# StepperMotorDrivers.net
KiCad netlist of a schematic drawn in Altium Designer
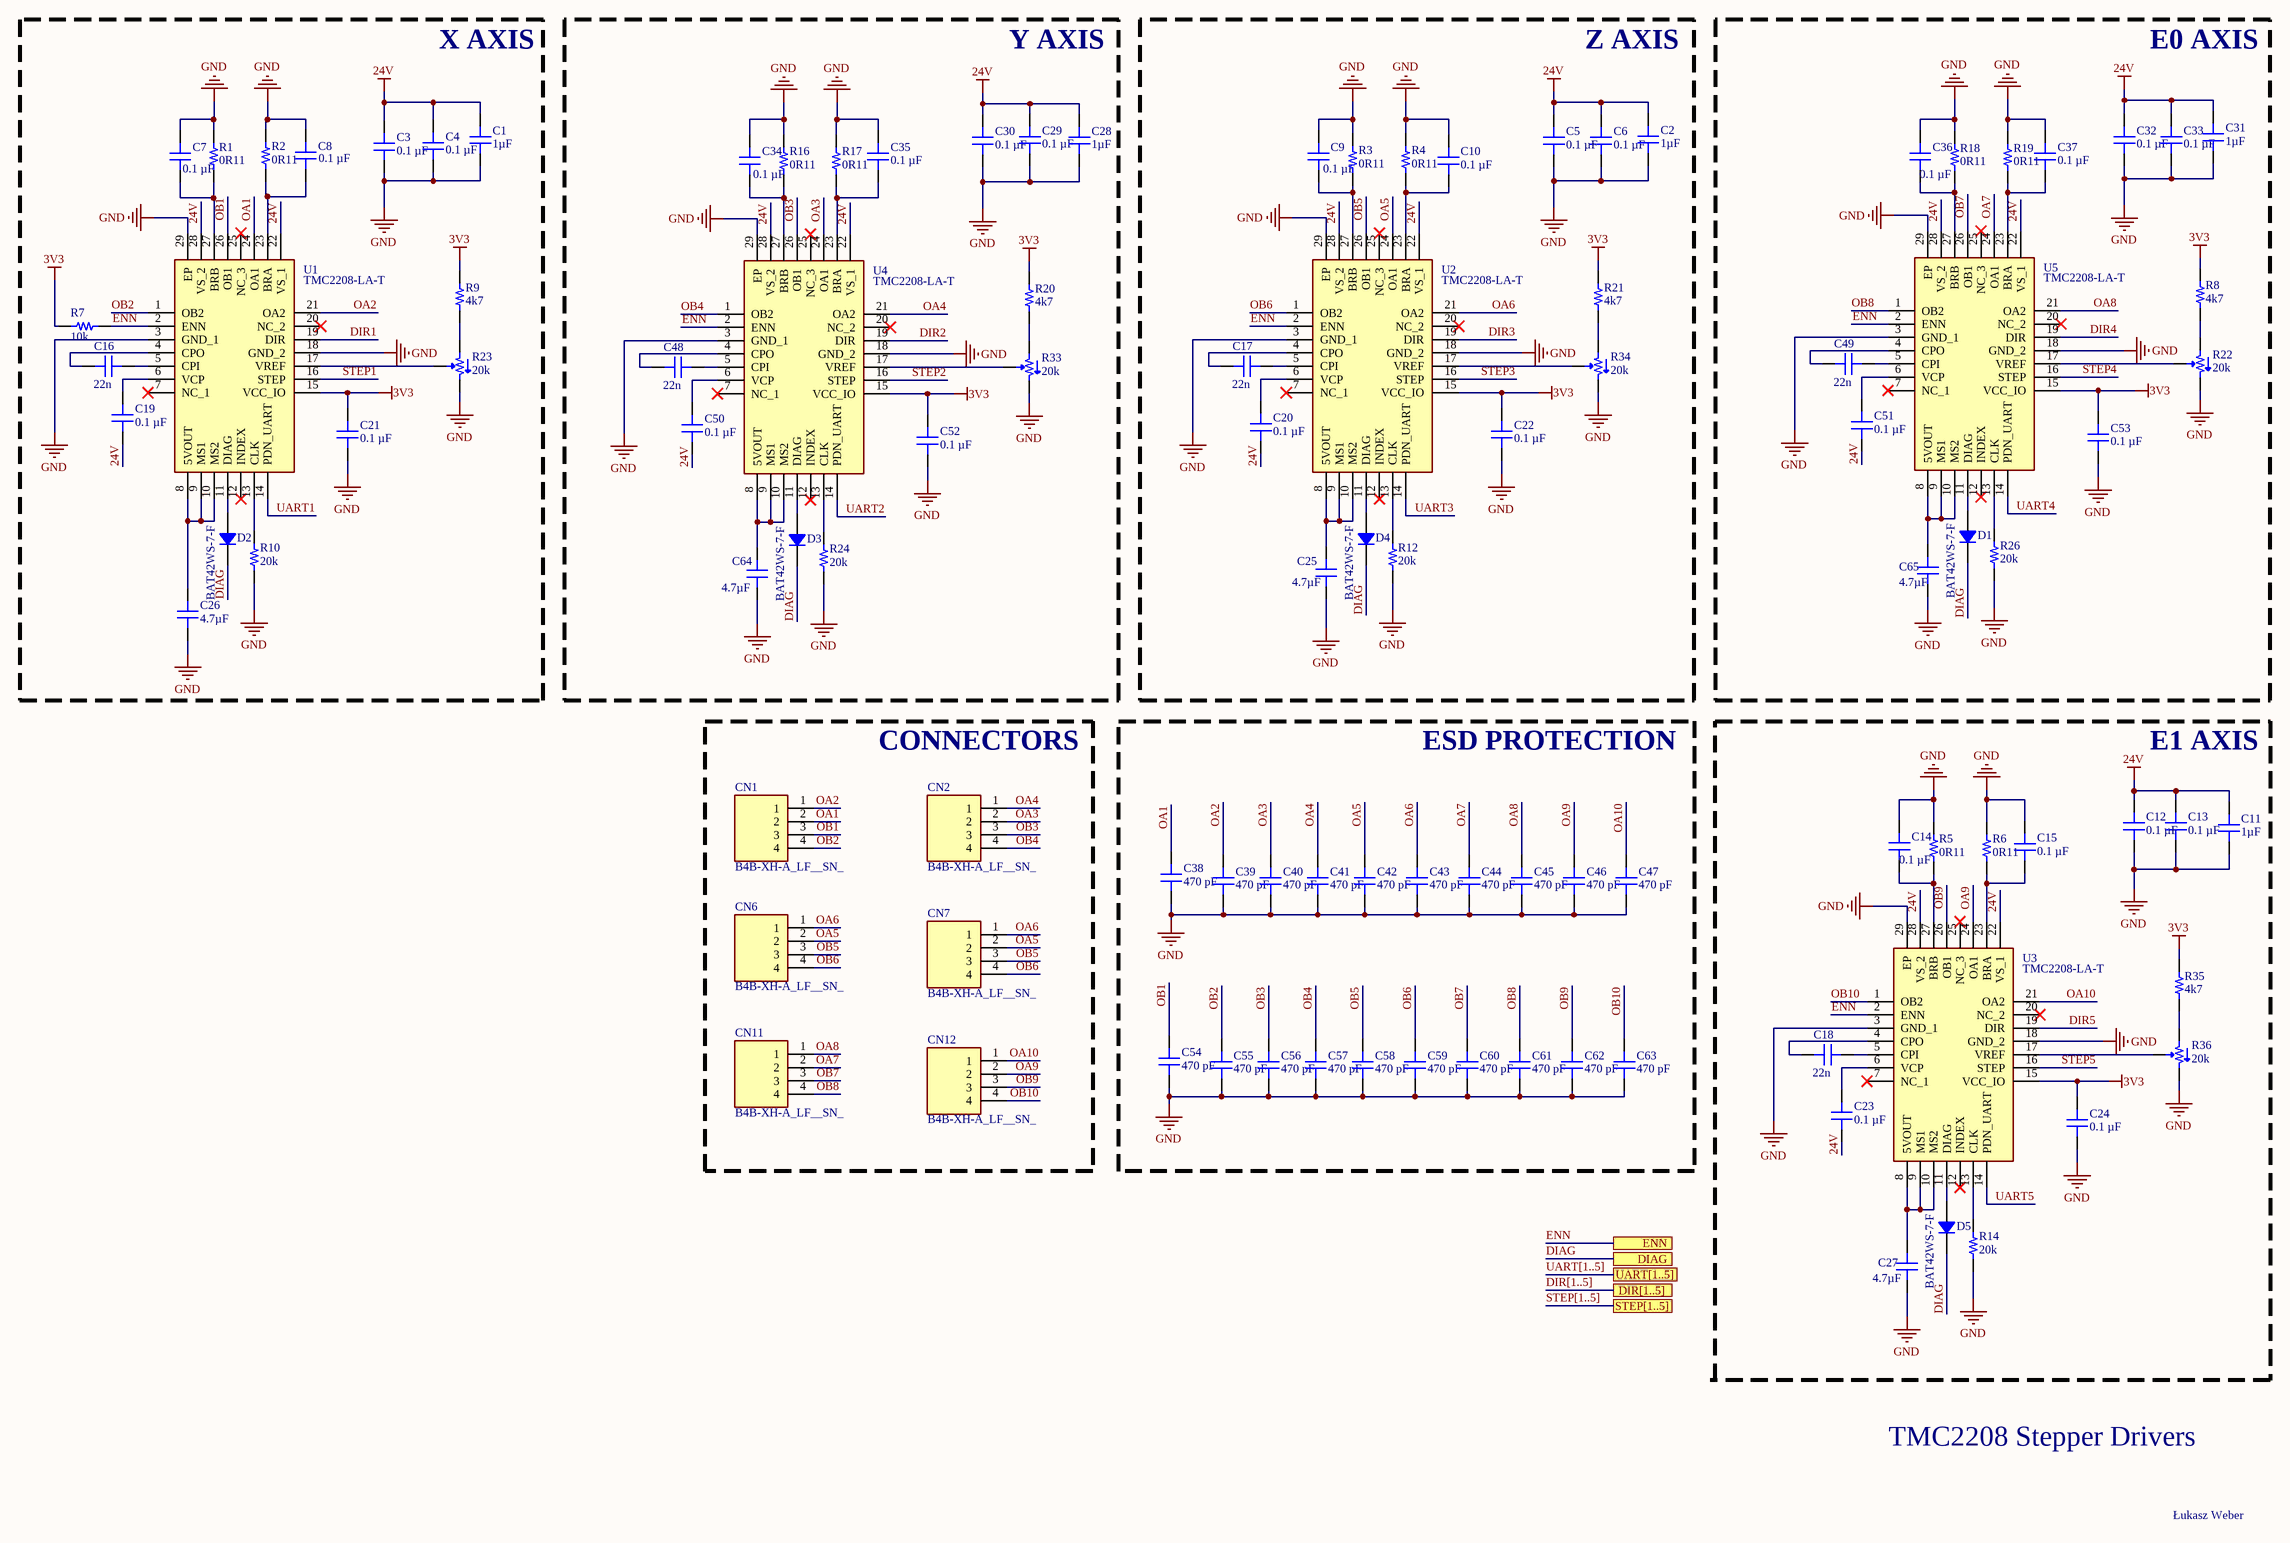
[diagram p0: StepperMotorDrivers.SchDoc]

(export (version "E")
  (design (tool "Eeschema 10.0.6"))
  (components
    (comp (ref "C1")
      (value "1µF")
      (footprint "CAP 0603_1608")
      (description "CAP CER 1UF 50V X7R 0603")
      (fields (field (name "PART NUMBER") "06035C105KAT2A") (field (name "MANUFACTURER") "AVX Corporation"))
      (libsource (lib "Celestial Altium Library - altium_library") (part "Capacitor"))
    )
    (comp (ref "C2")
      (value "1µF")
      (footprint "CAP 0603_1608")
      (description "CAP CER 1UF 50V X7R 0603")
      (fields (field (name "PART NUMBER") "06035C105KAT2A") (field (name "MANUFACTURER") "AVX Corporation"))
      (libsource (lib "Celestial Altium Library - altium_library") (part "Capacitor"))
    )
    (comp (ref "C3")
      (value "0.1 µF")
      (footprint "CAP 0603_1608")
      (description "CAP CER 0.1UF 100V X7R 0603")
      (fields
        (field (name "PART NUMBER") "0603B104K101CT")
        (field (name "MANUFACTURER") "Walsin Technology Corporation")
      )
      (libsource (lib "Celestial Altium Library - altium_library") (part "Capacitor"))
    )
    (comp (ref "C4")
      (value "0.1 µF")
      (footprint "CAP 0603_1608")
      (description "CAP CER 0.1UF 100V X7R 0603")
      (fields
        (field (name "PART NUMBER") "0603B104K101CT")
        (field (name "MANUFACTURER") "Walsin Technology Corporation")
      )
      (libsource (lib "Celestial Altium Library - altium_library") (part "Capacitor"))
    )
    (comp (ref "C5")
      (value "0.1 µF")
      (footprint "CAP 0603_1608")
      (description "CAP CER 0.1UF 100V X7R 0603")
      (fields
        (field (name "PART NUMBER") "0603B104K101CT")
        (field (name "MANUFACTURER") "Walsin Technology Corporation")
      )
      (libsource (lib "Celestial Altium Library - altium_library") (part "Capacitor"))
    )
    (comp (ref "C6")
      (value "0.1 µF")
      (footprint "CAP 0603_1608")
      (description "CAP CER 0.1UF 100V X7R 0603")
      (fields
        (field (name "PART NUMBER") "0603B104K101CT")
        (field (name "MANUFACTURER") "Walsin Technology Corporation")
      )
      (libsource (lib "Celestial Altium Library - altium_library") (part "Capacitor"))
    )
    (comp (ref "C7")
      (value "0.1 µF")
      (footprint "CAP 0603_1608")
      (description "CAP CER 0.1UF 100V X7R 0603")
      (fields
        (field (name "PART NUMBER") "0603B104K101CT")
        (field (name "MANUFACTURER") "Walsin Technology Corporation")
      )
      (libsource (lib "Celestial Altium Library - altium_library") (part "Capacitor"))
    )
    (comp (ref "C8")
      (value "0.1 µF")
      (footprint "CAP 0603_1608")
      (description "CAP CER 0.1UF 100V X7R 0603")
      (fields
        (field (name "PART NUMBER") "0603B104K101CT")
        (field (name "MANUFACTURER") "Walsin Technology Corporation")
      )
      (libsource (lib "Celestial Altium Library - altium_library") (part "Capacitor"))
    )
    (comp (ref "C9")
      (value "0.1 µF")
      (footprint "CAP 0603_1608")
      (description "CAP CER 0.1UF 100V X7R 0603")
      (fields
        (field (name "PART NUMBER") "0603B104K101CT")
        (field (name "MANUFACTURER") "Walsin Technology Corporation")
      )
      (libsource (lib "Celestial Altium Library - altium_library") (part "Capacitor"))
    )
    (comp (ref "C10")
      (value "0.1 µF")
      (footprint "CAP 0603_1608")
      (description "CAP CER 0.1UF 100V X7R 0603")
      (fields
        (field (name "PART NUMBER") "0603B104K101CT")
        (field (name "MANUFACTURER") "Walsin Technology Corporation")
      )
      (libsource (lib "Celestial Altium Library - altium_library") (part "Capacitor"))
    )
    (comp (ref "C11")
      (value "1µF")
      (footprint "CAP 0603_1608")
      (description "CAP CER 1UF 50V X7R 0603")
      (fields (field (name "PART NUMBER") "06035C105KAT2A") (field (name "MANUFACTURER") "AVX Corporation"))
      (libsource (lib "Celestial Altium Library - altium_library") (part "Capacitor"))
    )
    (comp (ref "C12")
      (value "0.1 µF")
      (footprint "CAP 0603_1608")
      (description "CAP CER 0.1UF 100V X7R 0603")
      (fields
        (field (name "PART NUMBER") "0603B104K101CT")
        (field (name "MANUFACTURER") "Walsin Technology Corporation")
      )
      (libsource (lib "Celestial Altium Library - altium_library") (part "Capacitor"))
    )
    (comp (ref "C13")
      (value "0.1 µF")
      (footprint "CAP 0603_1608")
      (description "CAP CER 0.1UF 100V X7R 0603")
      (fields
        (field (name "PART NUMBER") "0603B104K101CT")
        (field (name "MANUFACTURER") "Walsin Technology Corporation")
      )
      (libsource (lib "Celestial Altium Library - altium_library") (part "Capacitor"))
    )
    (comp (ref "C14")
      (value "0.1 µF")
      (footprint "CAP 0603_1608")
      (description "CAP CER 0.1UF 100V X7R 0603")
      (fields
        (field (name "PART NUMBER") "0603B104K101CT")
        (field (name "MANUFACTURER") "Walsin Technology Corporation")
      )
      (libsource (lib "Celestial Altium Library - altium_library") (part "Capacitor"))
    )
    (comp (ref "C15")
      (value "0.1 µF")
      (footprint "CAP 0603_1608")
      (description "CAP CER 0.1UF 100V X7R 0603")
      (fields
        (field (name "PART NUMBER") "0603B104K101CT")
        (field (name "MANUFACTURER") "Walsin Technology Corporation")
      )
      (libsource (lib "Celestial Altium Library - altium_library") (part "Capacitor"))
    )
    (comp (ref "C16")
      (value "22n")
      (footprint "CAP 0603_1608")
      (description "CAP CER 2200PF 50V NP0 0603")
      (fields (field (name "PART NUMBER") "C0603C222G5GAC7867") (field (name "MANUFACTURER") "KEMET"))
      (libsource (lib "Celestial Altium Library - altium_library") (part "Capacitor"))
    )
    (comp (ref "C17")
      (value "22n")
      (footprint "CAP 0603_1608")
      (description "CAP CER 2200PF 50V NP0 0603")
      (fields (field (name "PART NUMBER") "C0603C222G5GAC7867") (field (name "MANUFACTURER") "KEMET"))
      (libsource (lib "Celestial Altium Library - altium_library") (part "Capacitor"))
    )
    (comp (ref "C18")
      (value "22n")
      (footprint "CAP 0603_1608")
      (description "CAP CER 2200PF 50V NP0 0603")
      (fields (field (name "PART NUMBER") "C0603C222G5GAC7867") (field (name "MANUFACTURER") "KEMET"))
      (libsource (lib "Celestial Altium Library - altium_library") (part "Capacitor"))
    )
    (comp (ref "C19")
      (value "0.1 µF")
      (footprint "CAP 0603_1608")
      (description "CAP CER 0.1UF 100V X7R 0603")
      (fields
        (field (name "PART NUMBER") "0603B104K101CT")
        (field (name "MANUFACTURER") "Walsin Technology Corporation")
      )
      (libsource (lib "Celestial Altium Library - altium_library") (part "Capacitor"))
    )
    (comp (ref "C20")
      (value "0.1 µF")
      (footprint "CAP 0603_1608")
      (description "CAP CER 0.1UF 100V X7R 0603")
      (fields
        (field (name "PART NUMBER") "0603B104K101CT")
        (field (name "MANUFACTURER") "Walsin Technology Corporation")
      )
      (libsource (lib "Celestial Altium Library - altium_library") (part "Capacitor"))
    )
    (comp (ref "C21")
      (value "0.1 µF")
      (footprint "CAP 0603_1608")
      (description "CAP CER 0.1UF 100V X7R 0603")
      (fields
        (field (name "PART NUMBER") "0603B104K101CT")
        (field (name "MANUFACTURER") "Walsin Technology Corporation")
      )
      (libsource (lib "Celestial Altium Library - altium_library") (part "Capacitor"))
    )
    (comp (ref "C22")
      (value "0.1 µF")
      (footprint "CAP 0603_1608")
      (description "CAP CER 0.1UF 100V X7R 0603")
      (fields
        (field (name "PART NUMBER") "0603B104K101CT")
        (field (name "MANUFACTURER") "Walsin Technology Corporation")
      )
      (libsource (lib "Celestial Altium Library - altium_library") (part "Capacitor"))
    )
    (comp (ref "C23")
      (value "0.1 µF")
      (footprint "CAP 0603_1608")
      (description "CAP CER 0.1UF 100V X7R 0603")
      (fields
        (field (name "PART NUMBER") "0603B104K101CT")
        (field (name "MANUFACTURER") "Walsin Technology Corporation")
      )
      (libsource (lib "Celestial Altium Library - altium_library") (part "Capacitor"))
    )
    (comp (ref "C24")
      (value "0.1 µF")
      (footprint "CAP 0603_1608")
      (description "CAP CER 0.1UF 100V X7R 0603")
      (fields
        (field (name "PART NUMBER") "0603B104K101CT")
        (field (name "MANUFACTURER") "Walsin Technology Corporation")
      )
      (libsource (lib "Celestial Altium Library - altium_library") (part "Capacitor"))
    )
    (comp (ref "C25")
      (value "4.7µF")
      (footprint "CAP 0603_1608")
      (description "CAP CER 4.7UF 6.3V X5R 0603")
      (fields (field (name "PART NUMBER") "06036D475MAT2A") (field (name "MANUFACTURER") "AVX Corporation"))
      (libsource (lib "Celestial Altium Library - altium_library") (part "Capacitor"))
    )
    (comp (ref "C26")
      (value "4.7µF")
      (footprint "CAP 0603_1608")
      (description "CAP CER 4.7UF 6.3V X5R 0603")
      (fields (field (name "PART NUMBER") "06036D475MAT2A") (field (name "MANUFACTURER") "AVX Corporation"))
      (libsource (lib "Celestial Altium Library - altium_library") (part "Capacitor"))
    )
    (comp (ref "C27")
      (value "4.7µF")
      (footprint "CAP 0603_1608")
      (description "CAP CER 4.7UF 6.3V X5R 0603")
      (fields (field (name "PART NUMBER") "06036D475MAT2A") (field (name "MANUFACTURER") "AVX Corporation"))
      (libsource (lib "Celestial Altium Library - altium_library") (part "Capacitor"))
    )
    (comp (ref "C28")
      (value "1µF")
      (footprint "CAP 0603_1608")
      (description "CAP CER 1UF 50V X7R 0603")
      (fields (field (name "PART NUMBER") "06035C105KAT2A") (field (name "MANUFACTURER") "AVX Corporation"))
      (libsource (lib "Celestial Altium Library - altium_library") (part "Capacitor"))
    )
    (comp (ref "C29")
      (value "0.1 µF")
      (footprint "CAP 0603_1608")
      (description "CAP CER 0.1UF 100V X7R 0603")
      (fields
        (field (name "PART NUMBER") "0603B104K101CT")
        (field (name "MANUFACTURER") "Walsin Technology Corporation")
      )
      (libsource (lib "Celestial Altium Library - altium_library") (part "Capacitor"))
    )
    (comp (ref "C30")
      (value "0.1 µF")
      (footprint "CAP 0603_1608")
      (description "CAP CER 0.1UF 100V X7R 0603")
      (fields
        (field (name "PART NUMBER") "0603B104K101CT")
        (field (name "MANUFACTURER") "Walsin Technology Corporation")
      )
      (libsource (lib "Celestial Altium Library - altium_library") (part "Capacitor"))
    )
    (comp (ref "C31")
      (value "1µF")
      (footprint "CAP 0603_1608")
      (description "CAP CER 1UF 50V X7R 0603")
      (fields (field (name "PART NUMBER") "06035C105KAT2A") (field (name "MANUFACTURER") "AVX Corporation"))
      (libsource (lib "Celestial Altium Library - altium_library") (part "Capacitor"))
    )
    (comp (ref "C32")
      (value "0.1 µF")
      (footprint "CAP 0603_1608")
      (description "CAP CER 0.1UF 100V X7R 0603")
      (fields
        (field (name "PART NUMBER") "0603B104K101CT")
        (field (name "MANUFACTURER") "Walsin Technology Corporation")
      )
      (libsource (lib "Celestial Altium Library - altium_library") (part "Capacitor"))
    )
    (comp (ref "C33")
      (value "0.1 µF")
      (footprint "CAP 0603_1608")
      (description "CAP CER 0.1UF 100V X7R 0603")
      (fields
        (field (name "PART NUMBER") "0603B104K101CT")
        (field (name "MANUFACTURER") "Walsin Technology Corporation")
      )
      (libsource (lib "Celestial Altium Library - altium_library") (part "Capacitor"))
    )
    (comp (ref "C34")
      (value "0.1 µF")
      (footprint "CAP 0603_1608")
      (description "CAP CER 0.1UF 100V X7R 0603")
      (fields
        (field (name "PART NUMBER") "0603B104K101CT")
        (field (name "MANUFACTURER") "Walsin Technology Corporation")
      )
      (libsource (lib "Celestial Altium Library - altium_library") (part "Capacitor"))
    )
    (comp (ref "C35")
      (value "0.1 µF")
      (footprint "CAP 0603_1608")
      (description "CAP CER 0.1UF 100V X7R 0603")
      (fields
        (field (name "PART NUMBER") "0603B104K101CT")
        (field (name "MANUFACTURER") "Walsin Technology Corporation")
      )
      (libsource (lib "Celestial Altium Library - altium_library") (part "Capacitor"))
    )
    (comp (ref "C36")
      (value "0.1 µF")
      (footprint "CAP 0603_1608")
      (description "CAP CER 0.1UF 100V X7R 0603")
      (fields
        (field (name "PART NUMBER") "0603B104K101CT")
        (field (name "MANUFACTURER") "Walsin Technology Corporation")
      )
      (libsource (lib "Celestial Altium Library - altium_library") (part "Capacitor"))
    )
    (comp (ref "C37")
      (value "0.1 µF")
      (footprint "CAP 0603_1608")
      (description "CAP CER 0.1UF 100V X7R 0603")
      (fields
        (field (name "PART NUMBER") "0603B104K101CT")
        (field (name "MANUFACTURER") "Walsin Technology Corporation")
      )
      (libsource (lib "Celestial Altium Library - altium_library") (part "Capacitor"))
    )
    (comp (ref "C38")
      (value "470 pF")
      (footprint "CAP 0603_1608")
      (description "CAP CER 0603 470PF 5% X7R 50V FL")
      (fields (field (name "PART NUMBER") "C0603X471J5RAC7867") (field (name "MANUFACTURER") "KEMET"))
      (libsource (lib "Celestial Altium Library - altium_library") (part "Capacitor"))
    )
    (comp (ref "C39")
      (value "470 pF")
      (footprint "CAP 0603_1608")
      (description "CAP CER 0603 470PF 5% X7R 50V FL")
      (fields (field (name "PART NUMBER") "C0603X471J5RAC7867") (field (name "MANUFACTURER") "KEMET"))
      (libsource (lib "Celestial Altium Library - altium_library") (part "Capacitor"))
    )
    (comp (ref "C40")
      (value "470 pF")
      (footprint "CAP 0603_1608")
      (description "CAP CER 0603 470PF 5% X7R 50V FL")
      (fields (field (name "PART NUMBER") "C0603X471J5RAC7867") (field (name "MANUFACTURER") "KEMET"))
      (libsource (lib "Celestial Altium Library - altium_library") (part "Capacitor"))
    )
    (comp (ref "C41")
      (value "470 pF")
      (footprint "CAP 0603_1608")
      (description "CAP CER 0603 470PF 5% X7R 50V FL")
      (fields (field (name "PART NUMBER") "C0603X471J5RAC7867") (field (name "MANUFACTURER") "KEMET"))
      (libsource (lib "Celestial Altium Library - altium_library") (part "Capacitor"))
    )
    (comp (ref "C42")
      (value "470 pF")
      (footprint "CAP 0603_1608")
      (description "CAP CER 0603 470PF 5% X7R 50V FL")
      (fields (field (name "PART NUMBER") "C0603X471J5RAC7867") (field (name "MANUFACTURER") "KEMET"))
      (libsource (lib "Celestial Altium Library - altium_library") (part "Capacitor"))
    )
    (comp (ref "C43")
      (value "470 pF")
      (footprint "CAP 0603_1608")
      (description "CAP CER 0603 470PF 5% X7R 50V FL")
      (fields (field (name "PART NUMBER") "C0603X471J5RAC7867") (field (name "MANUFACTURER") "KEMET"))
      (libsource (lib "Celestial Altium Library - altium_library") (part "Capacitor"))
    )
    (comp (ref "C44")
      (value "470 pF")
      (footprint "CAP 0603_1608")
      (description "CAP CER 0603 470PF 5% X7R 50V FL")
      (fields (field (name "PART NUMBER") "C0603X471J5RAC7867") (field (name "MANUFACTURER") "KEMET"))
      (libsource (lib "Celestial Altium Library - altium_library") (part "Capacitor"))
    )
    (comp (ref "C45")
      (value "470 pF")
      (footprint "CAP 0603_1608")
      (description "CAP CER 0603 470PF 5% X7R 50V FL")
      (fields (field (name "PART NUMBER") "C0603X471J5RAC7867") (field (name "MANUFACTURER") "KEMET"))
      (libsource (lib "Celestial Altium Library - altium_library") (part "Capacitor"))
    )
    (comp (ref "C46")
      (value "470 pF")
      (footprint "CAP 0603_1608")
      (description "CAP CER 0603 470PF 5% X7R 50V FL")
      (fields (field (name "PART NUMBER") "C0603X471J5RAC7867") (field (name "MANUFACTURER") "KEMET"))
      (libsource (lib "Celestial Altium Library - altium_library") (part "Capacitor"))
    )
    (comp (ref "C47")
      (value "470 pF")
      (footprint "CAP 0603_1608")
      (description "CAP CER 0603 470PF 5% X7R 50V FL")
      (fields (field (name "PART NUMBER") "C0603X471J5RAC7867") (field (name "MANUFACTURER") "KEMET"))
      (libsource (lib "Celestial Altium Library - altium_library") (part "Capacitor"))
    )
    (comp (ref "C48")
      (value "22n")
      (footprint "CAP 0603_1608")
      (description "CAP CER 2200PF 50V NP0 0603")
      (fields (field (name "PART NUMBER") "C0603C222G5GAC7867") (field (name "MANUFACTURER") "KEMET"))
      (libsource (lib "Celestial Altium Library - altium_library") (part "Capacitor"))
    )
    (comp (ref "C49")
      (value "22n")
      (footprint "CAP 0603_1608")
      (description "CAP CER 2200PF 50V NP0 0603")
      (fields (field (name "PART NUMBER") "C0603C222G5GAC7867") (field (name "MANUFACTURER") "KEMET"))
      (libsource (lib "Celestial Altium Library - altium_library") (part "Capacitor"))
    )
    (comp (ref "C50")
      (value "0.1 µF")
      (footprint "CAP 0603_1608")
      (description "CAP CER 0.1UF 100V X7R 0603")
      (fields
        (field (name "PART NUMBER") "0603B104K101CT")
        (field (name "MANUFACTURER") "Walsin Technology Corporation")
      )
      (libsource (lib "Celestial Altium Library - altium_library") (part "Capacitor"))
    )
    (comp (ref "C51")
      (value "0.1 µF")
      (footprint "CAP 0603_1608")
      (description "CAP CER 0.1UF 100V X7R 0603")
      (fields
        (field (name "PART NUMBER") "0603B104K101CT")
        (field (name "MANUFACTURER") "Walsin Technology Corporation")
      )
      (libsource (lib "Celestial Altium Library - altium_library") (part "Capacitor"))
    )
    (comp (ref "C52")
      (value "0.1 µF")
      (footprint "CAP 0603_1608")
      (description "CAP CER 0.1UF 100V X7R 0603")
      (fields
        (field (name "PART NUMBER") "0603B104K101CT")
        (field (name "MANUFACTURER") "Walsin Technology Corporation")
      )
      (libsource (lib "Celestial Altium Library - altium_library") (part "Capacitor"))
    )
    (comp (ref "C53")
      (value "0.1 µF")
      (footprint "CAP 0603_1608")
      (description "CAP CER 0.1UF 100V X7R 0603")
      (fields
        (field (name "PART NUMBER") "0603B104K101CT")
        (field (name "MANUFACTURER") "Walsin Technology Corporation")
      )
      (libsource (lib "Celestial Altium Library - altium_library") (part "Capacitor"))
    )
    (comp (ref "C54")
      (value "470 pF")
      (footprint "CAP 0603_1608")
      (description "CAP CER 0603 470PF 5% X7R 50V FL")
      (fields (field (name "PART NUMBER") "C0603X471J5RAC7867") (field (name "MANUFACTURER") "KEMET"))
      (libsource (lib "Celestial Altium Library - altium_library") (part "Capacitor"))
    )
    (comp (ref "C55")
      (value "470 pF")
      (footprint "CAP 0603_1608")
      (description "CAP CER 0603 470PF 5% X7R 50V FL")
      (fields (field (name "PART NUMBER") "C0603X471J5RAC7867") (field (name "MANUFACTURER") "KEMET"))
      (libsource (lib "Celestial Altium Library - altium_library") (part "Capacitor"))
    )
    (comp (ref "C56")
      (value "470 pF")
      (footprint "CAP 0603_1608")
      (description "CAP CER 0603 470PF 5% X7R 50V FL")
      (fields (field (name "PART NUMBER") "C0603X471J5RAC7867") (field (name "MANUFACTURER") "KEMET"))
      (libsource (lib "Celestial Altium Library - altium_library") (part "Capacitor"))
    )
    (comp (ref "C57")
      (value "470 pF")
      (footprint "CAP 0603_1608")
      (description "CAP CER 0603 470PF 5% X7R 50V FL")
      (fields (field (name "PART NUMBER") "C0603X471J5RAC7867") (field (name "MANUFACTURER") "KEMET"))
      (libsource (lib "Celestial Altium Library - altium_library") (part "Capacitor"))
    )
    (comp (ref "C58")
      (value "470 pF")
      (footprint "CAP 0603_1608")
      (description "CAP CER 0603 470PF 5% X7R 50V FL")
      (fields (field (name "PART NUMBER") "C0603X471J5RAC7867") (field (name "MANUFACTURER") "KEMET"))
      (libsource (lib "Celestial Altium Library - altium_library") (part "Capacitor"))
    )
    (comp (ref "C59")
      (value "470 pF")
      (footprint "CAP 0603_1608")
      (description "CAP CER 0603 470PF 5% X7R 50V FL")
      (fields (field (name "PART NUMBER") "C0603X471J5RAC7867") (field (name "MANUFACTURER") "KEMET"))
      (libsource (lib "Celestial Altium Library - altium_library") (part "Capacitor"))
    )
    (comp (ref "C60")
      (value "470 pF")
      (footprint "CAP 0603_1608")
      (description "CAP CER 0603 470PF 5% X7R 50V FL")
      (fields (field (name "PART NUMBER") "C0603X471J5RAC7867") (field (name "MANUFACTURER") "KEMET"))
      (libsource (lib "Celestial Altium Library - altium_library") (part "Capacitor"))
    )
    (comp (ref "C61")
      (value "470 pF")
      (footprint "CAP 0603_1608")
      (description "CAP CER 0603 470PF 5% X7R 50V FL")
      (fields (field (name "PART NUMBER") "C0603X471J5RAC7867") (field (name "MANUFACTURER") "KEMET"))
      (libsource (lib "Celestial Altium Library - altium_library") (part "Capacitor"))
    )
    (comp (ref "C62")
      (value "470 pF")
      (footprint "CAP 0603_1608")
      (description "CAP CER 0603 470PF 5% X7R 50V FL")
      (fields (field (name "PART NUMBER") "C0603X471J5RAC7867") (field (name "MANUFACTURER") "KEMET"))
      (libsource (lib "Celestial Altium Library - altium_library") (part "Capacitor"))
    )
    (comp (ref "C63")
      (value "470 pF")
      (footprint "CAP 0603_1608")
      (description "CAP CER 0603 470PF 5% X7R 50V FL")
      (fields (field (name "PART NUMBER") "C0603X471J5RAC7867") (field (name "MANUFACTURER") "KEMET"))
      (libsource (lib "Celestial Altium Library - altium_library") (part "Capacitor"))
    )
    (comp (ref "C64")
      (value "4.7µF")
      (footprint "CAP 0603_1608")
      (description "CAP CER 4.7UF 6.3V X5R 0603")
      (fields (field (name "PART NUMBER") "06036D475MAT2A") (field (name "MANUFACTURER") "AVX Corporation"))
      (libsource (lib "Celestial Altium Library - altium_library") (part "Capacitor"))
    )
    (comp (ref "C65")
      (value "4.7µF")
      (footprint "CAP 0603_1608")
      (description "CAP CER 4.7UF 6.3V X5R 0603")
      (fields (field (name "PART NUMBER") "06036D475MAT2A") (field (name "MANUFACTURER") "AVX Corporation"))
      (libsource (lib "Celestial Altium Library - altium_library") (part "Capacitor"))
    )
    (comp (ref "CN1")
      (value "B4B-XH-A_LF__SN_")
      (footprint "Power Driver:B4BXHALFSN")
      (description "Connector")
      (fields (field (name "MANUFACTURER_PART_NUMBER") "B4B-XH-A(LF)(SN)"))
      (libsource (lib "*") (part "B4B-XH-A_LF__SN_"))
    )
    (comp (ref "CN2")
      (value "B4B-XH-A_LF__SN_")
      (footprint "Power Driver:B4BXHALFSN")
      (description "Connector")
      (fields (field (name "MANUFACTURER_PART_NUMBER") "B4B-XH-A(LF)(SN)"))
      (libsource (lib "*") (part "B4B-XH-A_LF__SN_"))
    )
    (comp (ref "CN6")
      (value "B4B-XH-A_LF__SN_")
      (footprint "Power Driver:B4BXHALFSN")
      (description "Connector")
      (fields (field (name "MANUFACTURER_PART_NUMBER") "B4B-XH-A(LF)(SN)"))
      (libsource (lib "*") (part "B4B-XH-A_LF__SN_"))
    )
    (comp (ref "CN7")
      (value "B4B-XH-A_LF__SN_")
      (footprint "Power Driver:B4BXHALFSN")
      (description "Connector")
      (fields (field (name "MANUFACTURER_PART_NUMBER") "B4B-XH-A(LF)(SN)"))
      (libsource (lib "*") (part "B4B-XH-A_LF__SN_"))
    )
    (comp (ref "CN11")
      (value "B4B-XH-A_LF__SN_")
      (footprint "Power Driver:B4BXHALFSN")
      (description "Connector")
      (fields (field (name "MANUFACTURER_PART_NUMBER") "B4B-XH-A(LF)(SN)"))
      (libsource (lib "*") (part "B4B-XH-A_LF__SN_"))
    )
    (comp (ref "CN12")
      (value "B4B-XH-A_LF__SN_")
      (footprint "Power Driver:B4BXHALFSN")
      (description "Connector")
      (fields (field (name "MANUFACTURER_PART_NUMBER") "B4B-XH-A(LF)(SN)"))
      (libsource (lib "*") (part "B4B-XH-A_LF__SN_"))
    )
    (comp (ref "D1")
      (value "BAT42WS-7-F")
      (footprint "SOD323")
      (description "DIODE SCHOTTKY 30V 200MA SOD323")
      (fields (field (name "MANUFACTURER") "Diodes Incorporated"))
      (libsource (lib "Celestial Altium Library - altium_library") (part "Diode"))
    )
    (comp (ref "D2")
      (value "BAT42WS-7-F")
      (footprint "SOD323")
      (description "DIODE SCHOTTKY 30V 200MA SOD323")
      (fields (field (name "MANUFACTURER") "Diodes Incorporated"))
      (libsource (lib "Celestial Altium Library - altium_library") (part "Diode"))
    )
    (comp (ref "D3")
      (value "BAT42WS-7-F")
      (footprint "SOD323")
      (description "DIODE SCHOTTKY 30V 200MA SOD323")
      (fields (field (name "MANUFACTURER") "Diodes Incorporated"))
      (libsource (lib "Celestial Altium Library - altium_library") (part "Diode"))
    )
    (comp (ref "D4")
      (value "BAT42WS-7-F")
      (footprint "SOD323")
      (description "DIODE SCHOTTKY 30V 200MA SOD323")
      (fields (field (name "MANUFACTURER") "Diodes Incorporated"))
      (libsource (lib "Celestial Altium Library - altium_library") (part "Diode"))
    )
    (comp (ref "D5")
      (value "BAT42WS-7-F")
      (footprint "SOD323")
      (description "DIODE SCHOTTKY 30V 200MA SOD323")
      (fields (field (name "MANUFACTURER") "Diodes Incorporated"))
      (libsource (lib "Celestial Altium Library - altium_library") (part "Diode"))
    )
    (comp (ref "R1")
      (value "0R11")
      (footprint "RES 0805_2012")
      (description "RES 0.15 OHM 1% 1/4W 0805")
      (fields
        (field (name "PART NUMBER") "ERJ-U6SFR15V")
        (field (name "MANUFACTURER") "Panasonic Electronic Components")
      )
      (libsource (lib "Celestial Altium Library - altium_library") (part "Resistor"))
    )
    (comp (ref "R2")
      (value "0R11")
      (footprint "RES 0805_2012")
      (description "RES 0.15 OHM 1% 1/4W 0805")
      (fields
        (field (name "PART NUMBER") "ERJ-U6SFR15V")
        (field (name "MANUFACTURER") "Panasonic Electronic Components")
      )
      (libsource (lib "Celestial Altium Library - altium_library") (part "Resistor"))
    )
    (comp (ref "R3")
      (value "0R11")
      (footprint "RES 0805_2012")
      (description "RES 0.15 OHM 1% 1/4W 0805")
      (fields
        (field (name "PART NUMBER") "ERJ-U6SFR15V")
        (field (name "MANUFACTURER") "Panasonic Electronic Components")
      )
      (libsource (lib "Celestial Altium Library - altium_library") (part "Resistor"))
    )
    (comp (ref "R4")
      (value "0R11")
      (footprint "RES 0805_2012")
      (description "RES 0.15 OHM 1% 1/4W 0805")
      (fields
        (field (name "PART NUMBER") "ERJ-U6SFR15V")
        (field (name "MANUFACTURER") "Panasonic Electronic Components")
      )
      (libsource (lib "Celestial Altium Library - altium_library") (part "Resistor"))
    )
    (comp (ref "R5")
      (value "0R11")
      (footprint "RES 0805_2012")
      (description "RES 0.15 OHM 1% 1/4W 0805")
      (fields
        (field (name "PART NUMBER") "ERJ-U6SFR15V")
        (field (name "MANUFACTURER") "Panasonic Electronic Components")
      )
      (libsource (lib "Celestial Altium Library - altium_library") (part "Resistor"))
    )
    (comp (ref "R6")
      (value "0R11")
      (footprint "RES 0805_2012")
      (description "RES 0.15 OHM 1% 1/4W 0805")
      (fields
        (field (name "PART NUMBER") "ERJ-U6SFR15V")
        (field (name "MANUFACTURER") "Panasonic Electronic Components")
      )
      (libsource (lib "Celestial Altium Library - altium_library") (part "Resistor"))
    )
    (comp (ref "R7")
      (value "10k")
      (footprint "RES 0603_1608")
      (description "RES 20K OHM 1% 1/4W 0603")
      (fields
        (field (name "PART NUMBER") "ERJ-UP3F2002V")
        (field (name "MANUFACTURER") "Panasonic Electronic Components")
      )
      (libsource (lib "Celestial Altium Library - altium_library") (part "Resistor"))
    )
    (comp (ref "R8")
      (value "4k7")
      (footprint "RES 0603_1608")
      (description "RES 20K OHM 1% 1/4W 0603")
      (fields
        (field (name "PART NUMBER") "ERJ-UP3F2002V")
        (field (name "MANUFACTURER") "Panasonic Electronic Components")
      )
      (libsource (lib "Celestial Altium Library - altium_library") (part "Resistor"))
    )
    (comp (ref "R9")
      (value "4k7")
      (footprint "RES 0603_1608")
      (description "RES 20K OHM 1% 1/4W 0603")
      (fields
        (field (name "PART NUMBER") "ERJ-UP3F2002V")
        (field (name "MANUFACTURER") "Panasonic Electronic Components")
      )
      (libsource (lib "Celestial Altium Library - altium_library") (part "Resistor"))
    )
    (comp (ref "R10")
      (value "20k")
      (footprint "RES 0603_1608")
      (description "RES 20K OHM 1% 1/4W 0603")
      (fields
        (field (name "PART NUMBER") "ERJ-UP3F2002V")
        (field (name "MANUFACTURER") "Panasonic Electronic Components")
      )
      (libsource (lib "Celestial Altium Library - altium_library") (part "Resistor"))
    )
    (comp (ref "R12")
      (value "20k")
      (footprint "RES 0603_1608")
      (description "RES 20K OHM 1% 1/4W 0603")
      (fields
        (field (name "PART NUMBER") "ERJ-UP3F2002V")
        (field (name "MANUFACTURER") "Panasonic Electronic Components")
      )
      (libsource (lib "Celestial Altium Library - altium_library") (part "Resistor"))
    )
    (comp (ref "R14")
      (value "20k")
      (footprint "RES 0603_1608")
      (description "RES 20K OHM 1% 1/4W 0603")
      (fields
        (field (name "PART NUMBER") "ERJ-UP3F2002V")
        (field (name "MANUFACTURER") "Panasonic Electronic Components")
      )
      (libsource (lib "Celestial Altium Library - altium_library") (part "Resistor"))
    )
    (comp (ref "R16")
      (value "0R11")
      (footprint "RES 0805_2012")
      (description "RES 0.15 OHM 1% 1/4W 0805")
      (fields
        (field (name "PART NUMBER") "ERJ-U6SFR15V")
        (field (name "MANUFACTURER") "Panasonic Electronic Components")
      )
      (libsource (lib "Celestial Altium Library - altium_library") (part "Resistor"))
    )
    (comp (ref "R17")
      (value "0R11")
      (footprint "RES 0805_2012")
      (description "RES 0.15 OHM 1% 1/4W 0805")
      (fields
        (field (name "PART NUMBER") "ERJ-U6SFR15V")
        (field (name "MANUFACTURER") "Panasonic Electronic Components")
      )
      (libsource (lib "Celestial Altium Library - altium_library") (part "Resistor"))
    )
    (comp (ref "R18")
      (value "0R11")
      (footprint "RES 0805_2012")
      (description "RES 0.15 OHM 1% 1/4W 0805")
      (fields
        (field (name "PART NUMBER") "ERJ-U6SFR15V")
        (field (name "MANUFACTURER") "Panasonic Electronic Components")
      )
      (libsource (lib "Celestial Altium Library - altium_library") (part "Resistor"))
    )
    (comp (ref "R19")
      (value "0R11")
      (footprint "RES 0805_2012")
      (description "RES 0.15 OHM 1% 1/4W 0805")
      (fields
        (field (name "PART NUMBER") "ERJ-U6SFR15V")
        (field (name "MANUFACTURER") "Panasonic Electronic Components")
      )
      (libsource (lib "Celestial Altium Library - altium_library") (part "Resistor"))
    )
    (comp (ref "R20")
      (value "4k7")
      (footprint "RES 0603_1608")
      (description "RES 20K OHM 1% 1/4W 0603")
      (fields
        (field (name "PART NUMBER") "ERJ-UP3F2002V")
        (field (name "MANUFACTURER") "Panasonic Electronic Components")
      )
      (libsource (lib "Celestial Altium Library - altium_library") (part "Resistor"))
    )
    (comp (ref "R21")
      (value "4k7")
      (footprint "RES 0603_1608")
      (description "RES 20K OHM 1% 1/4W 0603")
      (fields
        (field (name "PART NUMBER") "ERJ-UP3F2002V")
        (field (name "MANUFACTURER") "Panasonic Electronic Components")
      )
      (libsource (lib "Celestial Altium Library - altium_library") (part "Resistor"))
    )
    (comp (ref "R22")
      (value "20k")
      (footprint "POT BOURNS TRIMPOT TC33")
      (description "TRIMMER 20K OHM 0.1W J LEAD TOP")
      (fields (field (name "PART NUMBER") "TC33X-2-203E") (field (name "MANUFACTURER") "Bourns Inc."))
      (libsource (lib "Celestial Altium Library - altium_library") (part "Potentiometer"))
    )
    (comp (ref "R23")
      (value "20k")
      (footprint "POT BOURNS TRIMPOT TC33")
      (description "TRIMMER 20K OHM 0.1W J LEAD TOP")
      (fields (field (name "PART NUMBER") "TC33X-2-203E") (field (name "MANUFACTURER") "Bourns Inc."))
      (libsource (lib "Celestial Altium Library - altium_library") (part "Potentiometer"))
    )
    (comp (ref "R24")
      (value "20k")
      (footprint "RES 0603_1608")
      (description "RES 20K OHM 1% 1/4W 0603")
      (fields
        (field (name "PART NUMBER") "ERJ-UP3F2002V")
        (field (name "MANUFACTURER") "Panasonic Electronic Components")
      )
      (libsource (lib "Celestial Altium Library - altium_library") (part "Resistor"))
    )
    (comp (ref "R26")
      (value "20k")
      (footprint "RES 0603_1608")
      (description "RES 20K OHM 1% 1/4W 0603")
      (fields
        (field (name "PART NUMBER") "ERJ-UP3F2002V")
        (field (name "MANUFACTURER") "Panasonic Electronic Components")
      )
      (libsource (lib "Celestial Altium Library - altium_library") (part "Resistor"))
    )
    (comp (ref "R33")
      (value "20k")
      (footprint "POT BOURNS TRIMPOT TC33")
      (description "TRIMMER 20K OHM 0.1W J LEAD TOP")
      (fields (field (name "PART NUMBER") "TC33X-2-203E") (field (name "MANUFACTURER") "Bourns Inc."))
      (libsource (lib "Celestial Altium Library - altium_library") (part "Potentiometer"))
    )
    (comp (ref "R34")
      (value "20k")
      (footprint "POT BOURNS TRIMPOT TC33")
      (description "TRIMMER 20K OHM 0.1W J LEAD TOP")
      (fields (field (name "PART NUMBER") "TC33X-2-203E") (field (name "MANUFACTURER") "Bourns Inc."))
      (libsource (lib "Celestial Altium Library - altium_library") (part "Potentiometer"))
    )
    (comp (ref "R35")
      (value "4k7")
      (footprint "RES 0603_1608")
      (description "RES 20K OHM 1% 1/4W 0603")
      (fields
        (field (name "PART NUMBER") "ERJ-UP3F2002V")
        (field (name "MANUFACTURER") "Panasonic Electronic Components")
      )
      (libsource (lib "Celestial Altium Library - altium_library") (part "Resistor"))
    )
    (comp (ref "R36")
      (value "20k")
      (footprint "POT BOURNS TRIMPOT TC33")
      (description "TRIMMER 20K OHM 0.1W J LEAD TOP")
      (fields (field (name "PART NUMBER") "TC33X-2-203E") (field (name "MANUFACTURER") "Bourns Inc."))
      (libsource (lib "Celestial Altium Library - altium_library") (part "Potentiometer"))
    )
    (comp (ref "U1")
      (value "TMC2208-LA-T")
      (footprint "Power Driver:QFN50P500X500X90-29N-D")
      (description "Integrated Circuit")
      (fields (field (name "MOUSER PART NUMBER") "700-TMC2208-LA-T"))
      (libsource (lib "*") (part "TMC2208-LA-T"))
    )
    (comp (ref "U2")
      (value "TMC2208-LA-T")
      (footprint "Power Driver:QFN50P500X500X90-29N-D")
      (description "Integrated Circuit")
      (fields (field (name "MOUSER PART NUMBER") "700-TMC2208-LA-T"))
      (libsource (lib "*") (part "TMC2208-LA-T"))
    )
    (comp (ref "U3")
      (value "TMC2208-LA-T")
      (footprint "Power Driver:QFN50P500X500X90-29N-D")
      (description "Integrated Circuit")
      (fields (field (name "MOUSER PART NUMBER") "700-TMC2208-LA-T"))
      (libsource (lib "*") (part "TMC2208-LA-T"))
    )
    (comp (ref "U4")
      (value "TMC2208-LA-T")
      (footprint "Power Driver:QFN50P500X500X90-29N-D")
      (description "Integrated Circuit")
      (fields (field (name "MOUSER PART NUMBER") "700-TMC2208-LA-T"))
      (libsource (lib "*") (part "TMC2208-LA-T"))
    )
    (comp (ref "U5")
      (value "TMC2208-LA-T")
      (footprint "Power Driver:QFN50P500X500X90-29N-D")
      (description "Integrated Circuit")
      (fields (field (name "MOUSER PART NUMBER") "700-TMC2208-LA-T"))
      (libsource (lib "*") (part "TMC2208-LA-T"))
    )
  )
  (nets
    (net (code "1") (name "/DIAG") (class "Default")
      (node (ref "D1") (pin "2") (pinfunction "2_2") (pintype "passive"))
      (node (ref "D2") (pin "2") (pinfunction "2_2") (pintype "passive"))
      (node (ref "D3") (pin "2") (pinfunction "2_2") (pintype "passive"))
      (node (ref "D4") (pin "2") (pinfunction "2_2") (pintype "passive"))
      (node (ref "D5") (pin "2") (pinfunction "2_2") (pintype "passive"))
    )
    (net (code "2") (name "/DIR1") (class "Default")
      (node (ref "U1") (pin "19") (pinfunction "DIR_19") (pintype "passive"))
    )
    (net (code "3") (name "/DIR2") (class "Default")
      (node (ref "U4") (pin "19") (pinfunction "DIR_19") (pintype "passive"))
    )
    (net (code "4") (name "/DIR3") (class "Default")
      (node (ref "U2") (pin "19") (pinfunction "DIR_19") (pintype "passive"))
    )
    (net (code "5") (name "/DIR4") (class "Default")
      (node (ref "U5") (pin "19") (pinfunction "DIR_19") (pintype "passive"))
    )
    (net (code "6") (name "/DIR5") (class "Default")
      (node (ref "U3") (pin "19") (pinfunction "DIR_19") (pintype "passive"))
    )
    (net (code "8") (name "/ENN") (class "Default")
      (node (ref "R7") (pin "1") (pinfunction "1_1") (pintype "passive"))
      (node (ref "U1") (pin "2") (pinfunction "ENN_2") (pintype "passive"))
      (node (ref "U2") (pin "2") (pinfunction "ENN_2") (pintype "passive"))
      (node (ref "U3") (pin "2") (pinfunction "ENN_2") (pintype "passive"))
      (node (ref "U4") (pin "2") (pinfunction "ENN_2") (pintype "passive"))
      (node (ref "U5") (pin "2") (pinfunction "ENN_2") (pintype "passive"))
    )
    (net (code "9") (name "/OA1") (class "Default")
      (node (ref "C38") (pin "2") (pinfunction "2_2") (pintype "passive"))
      (node (ref "CN1") (pin "2") (pinfunction "2_2") (pintype "passive"))
      (node (ref "U1") (pin "24") (pinfunction "OA1_24") (pintype "passive"))
    )
    (net (code "10") (name "/OA2") (class "Default")
      (node (ref "C39") (pin "2") (pinfunction "2_2") (pintype "passive"))
      (node (ref "CN1") (pin "1") (pinfunction "1_1") (pintype "passive"))
      (node (ref "U1") (pin "21") (pinfunction "OA2_21") (pintype "passive"))
    )
    (net (code "11") (name "/OA3") (class "Default")
      (node (ref "C40") (pin "2") (pinfunction "2_2") (pintype "passive"))
      (node (ref "CN2") (pin "2") (pinfunction "2_2") (pintype "passive"))
      (node (ref "U4") (pin "24") (pinfunction "OA1_24") (pintype "passive"))
    )
    (net (code "12") (name "/OA4") (class "Default")
      (node (ref "C41") (pin "2") (pinfunction "2_2") (pintype "passive"))
      (node (ref "CN2") (pin "1") (pinfunction "1_1") (pintype "passive"))
      (node (ref "U4") (pin "21") (pinfunction "OA2_21") (pintype "passive"))
    )
    (net (code "13") (name "/OA5") (class "Default")
      (node (ref "C42") (pin "2") (pinfunction "2_2") (pintype "passive"))
      (node (ref "CN6") (pin "2") (pinfunction "2_2") (pintype "passive"))
      (node (ref "CN7") (pin "2") (pinfunction "2_2") (pintype "passive"))
      (node (ref "U2") (pin "24") (pinfunction "OA1_24") (pintype "passive"))
    )
    (net (code "14") (name "/OA6") (class "Default")
      (node (ref "C43") (pin "2") (pinfunction "2_2") (pintype "passive"))
      (node (ref "CN6") (pin "1") (pinfunction "1_1") (pintype "passive"))
      (node (ref "CN7") (pin "1") (pinfunction "1_1") (pintype "passive"))
      (node (ref "U2") (pin "21") (pinfunction "OA2_21") (pintype "passive"))
    )
    (net (code "15") (name "/OA7") (class "Default")
      (node (ref "C44") (pin "2") (pinfunction "2_2") (pintype "passive"))
      (node (ref "CN11") (pin "2") (pinfunction "2_2") (pintype "passive"))
      (node (ref "U5") (pin "24") (pinfunction "OA1_24") (pintype "passive"))
    )
    (net (code "16") (name "/OA8") (class "Default")
      (node (ref "C45") (pin "2") (pinfunction "2_2") (pintype "passive"))
      (node (ref "CN11") (pin "1") (pinfunction "1_1") (pintype "passive"))
      (node (ref "U5") (pin "21") (pinfunction "OA2_21") (pintype "passive"))
    )
    (net (code "17") (name "/OA9") (class "Default")
      (node (ref "C46") (pin "2") (pinfunction "2_2") (pintype "passive"))
      (node (ref "CN12") (pin "2") (pinfunction "2_2") (pintype "passive"))
      (node (ref "U3") (pin "24") (pinfunction "OA1_24") (pintype "passive"))
    )
    (net (code "18") (name "/OA10") (class "Default")
      (node (ref "C47") (pin "2") (pinfunction "2_2") (pintype "passive"))
      (node (ref "CN12") (pin "1") (pinfunction "1_1") (pintype "passive"))
      (node (ref "U3") (pin "21") (pinfunction "OA2_21") (pintype "passive"))
    )
    (net (code "19") (name "/OB1") (class "Default")
      (node (ref "C54") (pin "2") (pinfunction "2_2") (pintype "passive"))
      (node (ref "CN1") (pin "3") (pinfunction "3_3") (pintype "passive"))
      (node (ref "U1") (pin "26") (pinfunction "OB1_26") (pintype "passive"))
    )
    (net (code "20") (name "/OB2") (class "Default")
      (node (ref "C55") (pin "2") (pinfunction "2_2") (pintype "passive"))
      (node (ref "CN1") (pin "4") (pinfunction "4_4") (pintype "passive"))
      (node (ref "U1") (pin "1") (pinfunction "OB2_1") (pintype "passive"))
    )
    (net (code "21") (name "/OB3") (class "Default")
      (node (ref "C56") (pin "2") (pinfunction "2_2") (pintype "passive"))
      (node (ref "CN2") (pin "3") (pinfunction "3_3") (pintype "passive"))
      (node (ref "U4") (pin "26") (pinfunction "OB1_26") (pintype "passive"))
    )
    (net (code "22") (name "/OB4") (class "Default")
      (node (ref "C57") (pin "2") (pinfunction "2_2") (pintype "passive"))
      (node (ref "CN2") (pin "4") (pinfunction "4_4") (pintype "passive"))
      (node (ref "U4") (pin "1") (pinfunction "OB2_1") (pintype "passive"))
    )
    (net (code "23") (name "/OB5") (class "Default")
      (node (ref "C58") (pin "2") (pinfunction "2_2") (pintype "passive"))
      (node (ref "CN6") (pin "3") (pinfunction "3_3") (pintype "passive"))
      (node (ref "CN7") (pin "3") (pinfunction "3_3") (pintype "passive"))
      (node (ref "U2") (pin "26") (pinfunction "OB1_26") (pintype "passive"))
    )
    (net (code "24") (name "/OB6") (class "Default")
      (node (ref "C59") (pin "2") (pinfunction "2_2") (pintype "passive"))
      (node (ref "CN6") (pin "4") (pinfunction "4_4") (pintype "passive"))
      (node (ref "CN7") (pin "4") (pinfunction "4_4") (pintype "passive"))
      (node (ref "U2") (pin "1") (pinfunction "OB2_1") (pintype "passive"))
    )
    (net (code "25") (name "/OB7") (class "Default")
      (node (ref "C60") (pin "2") (pinfunction "2_2") (pintype "passive"))
      (node (ref "CN11") (pin "3") (pinfunction "3_3") (pintype "passive"))
      (node (ref "U5") (pin "26") (pinfunction "OB1_26") (pintype "passive"))
    )
    (net (code "26") (name "/OB8") (class "Default")
      (node (ref "C61") (pin "2") (pinfunction "2_2") (pintype "passive"))
      (node (ref "CN11") (pin "4") (pinfunction "4_4") (pintype "passive"))
      (node (ref "U5") (pin "1") (pinfunction "OB2_1") (pintype "passive"))
    )
    (net (code "27") (name "/OB9") (class "Default")
      (node (ref "C62") (pin "2") (pinfunction "2_2") (pintype "passive"))
      (node (ref "CN12") (pin "3") (pinfunction "3_3") (pintype "passive"))
      (node (ref "U3") (pin "26") (pinfunction "OB1_26") (pintype "passive"))
    )
    (net (code "28") (name "/OB10") (class "Default")
      (node (ref "C63") (pin "2") (pinfunction "2_2") (pintype "passive"))
      (node (ref "CN12") (pin "4") (pinfunction "4_4") (pintype "passive"))
      (node (ref "U3") (pin "1") (pinfunction "OB2_1") (pintype "passive"))
    )
    (net (code "29") (name "/STEP1") (class "Default")
      (node (ref "U1") (pin "16") (pinfunction "STEP_16") (pintype "passive"))
    )
    (net (code "30") (name "/STEP2") (class "Default")
      (node (ref "U4") (pin "16") (pinfunction "STEP_16") (pintype "passive"))
    )
    (net (code "31") (name "/STEP3") (class "Default")
      (node (ref "U2") (pin "16") (pinfunction "STEP_16") (pintype "passive"))
    )
    (net (code "32") (name "/STEP4") (class "Default")
      (node (ref "U5") (pin "16") (pinfunction "STEP_16") (pintype "passive"))
    )
    (net (code "33") (name "/STEP5") (class "Default")
      (node (ref "U3") (pin "16") (pinfunction "STEP_16") (pintype "passive"))
    )
    (net (code "35") (name "/UART1") (class "Default")
      (node (ref "U1") (pin "14") (pinfunction "PDN_UART_14") (pintype "passive"))
    )
    (net (code "36") (name "/UART2") (class "Default")
      (node (ref "U4") (pin "14") (pinfunction "PDN_UART_14") (pintype "passive"))
    )
    (net (code "37") (name "/UART3") (class "Default")
      (node (ref "U2") (pin "14") (pinfunction "PDN_UART_14") (pintype "passive"))
    )
    (net (code "38") (name "/UART4") (class "Default")
      (node (ref "U5") (pin "14") (pinfunction "PDN_UART_14") (pintype "passive"))
    )
    (net (code "39") (name "/UART5") (class "Default")
      (node (ref "U3") (pin "14") (pinfunction "PDN_UART_14") (pintype "passive"))
    )
    (net (code "41") (name "3V3") (class "Default")
      (node (ref "C21") (pin "2") (pinfunction "2_2") (pintype "passive"))
      (node (ref "C22") (pin "2") (pinfunction "2_2") (pintype "passive"))
      (node (ref "C24") (pin "2") (pinfunction "2_2") (pintype "passive"))
      (node (ref "C52") (pin "2") (pinfunction "2_2") (pintype "passive"))
      (node (ref "C53") (pin "2") (pinfunction "2_2") (pintype "passive"))
      (node (ref "R20") (pin "1") (pinfunction "1_1") (pintype "passive"))
      (node (ref "R21") (pin "1") (pinfunction "1_1") (pintype "passive"))
      (node (ref "R35") (pin "1") (pinfunction "1_1") (pintype "passive"))
      (node (ref "R7") (pin "2") (pinfunction "2_2") (pintype "passive"))
      (node (ref "R8") (pin "1") (pinfunction "1_1") (pintype "passive"))
      (node (ref "R9") (pin "1") (pinfunction "1_1") (pintype "passive"))
      (node (ref "U1") (pin "15") (pinfunction "VCC_IO_15") (pintype "passive"))
      (node (ref "U2") (pin "15") (pinfunction "VCC_IO_15") (pintype "passive"))
      (node (ref "U3") (pin "15") (pinfunction "VCC_IO_15") (pintype "passive"))
      (node (ref "U4") (pin "15") (pinfunction "VCC_IO_15") (pintype "passive"))
      (node (ref "U5") (pin "15") (pinfunction "VCC_IO_15") (pintype "passive"))
    )
    (net (code "42") (name "24V") (class "Default")
      (node (ref "C1") (pin "2") (pinfunction "2_2") (pintype "passive"))
      (node (ref "C11") (pin "2") (pinfunction "2_2") (pintype "passive"))
      (node (ref "C12") (pin "2") (pinfunction "2_2") (pintype "passive"))
      (node (ref "C13") (pin "2") (pinfunction "2_2") (pintype "passive"))
      (node (ref "C19") (pin "1") (pinfunction "1_1") (pintype "passive"))
      (node (ref "C2") (pin "2") (pinfunction "2_2") (pintype "passive"))
      (node (ref "C20") (pin "1") (pinfunction "1_1") (pintype "passive"))
      (node (ref "C23") (pin "1") (pinfunction "1_1") (pintype "passive"))
      (node (ref "C28") (pin "2") (pinfunction "2_2") (pintype "passive"))
      (node (ref "C29") (pin "2") (pinfunction "2_2") (pintype "passive"))
      (node (ref "C3") (pin "2") (pinfunction "2_2") (pintype "passive"))
      (node (ref "C30") (pin "2") (pinfunction "2_2") (pintype "passive"))
      (node (ref "C31") (pin "2") (pinfunction "2_2") (pintype "passive"))
      (node (ref "C32") (pin "2") (pinfunction "2_2") (pintype "passive"))
      (node (ref "C33") (pin "2") (pinfunction "2_2") (pintype "passive"))
      (node (ref "C4") (pin "2") (pinfunction "2_2") (pintype "passive"))
      (node (ref "C5") (pin "2") (pinfunction "2_2") (pintype "passive"))
      (node (ref "C50") (pin "1") (pinfunction "1_1") (pintype "passive"))
      (node (ref "C51") (pin "1") (pinfunction "1_1") (pintype "passive"))
      (node (ref "C6") (pin "2") (pinfunction "2_2") (pintype "passive"))
      (node (ref "U1") (pin "22") (pinfunction "VS_1_22") (pintype "passive"))
      (node (ref "U1") (pin "28") (pinfunction "VS_2_28") (pintype "passive"))
      (node (ref "U2") (pin "22") (pinfunction "VS_1_22") (pintype "passive"))
      (node (ref "U2") (pin "28") (pinfunction "VS_2_28") (pintype "passive"))
      (node (ref "U3") (pin "22") (pinfunction "VS_1_22") (pintype "passive"))
      (node (ref "U3") (pin "28") (pinfunction "VS_2_28") (pintype "passive"))
      (node (ref "U4") (pin "22") (pinfunction "VS_1_22") (pintype "passive"))
      (node (ref "U4") (pin "28") (pinfunction "VS_2_28") (pintype "passive"))
      (node (ref "U5") (pin "22") (pinfunction "VS_1_22") (pintype "passive"))
      (node (ref "U5") (pin "28") (pinfunction "VS_2_28") (pintype "passive"))
    )
    (net (code "43") (name "GND") (class "Default")
      (node (ref "C1") (pin "1") (pinfunction "1_1") (pintype "passive"))
      (node (ref "C10") (pin "2") (pinfunction "2_2") (pintype "passive"))
      (node (ref "C11") (pin "1") (pinfunction "1_1") (pintype "passive"))
      (node (ref "C12") (pin "1") (pinfunction "1_1") (pintype "passive"))
      (node (ref "C13") (pin "1") (pinfunction "1_1") (pintype "passive"))
      (node (ref "C14") (pin "2") (pinfunction "2_2") (pintype "passive"))
      (node (ref "C15") (pin "2") (pinfunction "2_2") (pintype "passive"))
      (node (ref "C2") (pin "1") (pinfunction "1_1") (pintype "passive"))
      (node (ref "C21") (pin "1") (pinfunction "1_1") (pintype "passive"))
      (node (ref "C22") (pin "1") (pinfunction "1_1") (pintype "passive"))
      (node (ref "C24") (pin "1") (pinfunction "1_1") (pintype "passive"))
      (node (ref "C25") (pin "1") (pinfunction "1_1") (pintype "passive"))
      (node (ref "C26") (pin "1") (pinfunction "1_1") (pintype "passive"))
      (node (ref "C27") (pin "1") (pinfunction "1_1") (pintype "passive"))
      (node (ref "C28") (pin "1") (pinfunction "1_1") (pintype "passive"))
      (node (ref "C29") (pin "1") (pinfunction "1_1") (pintype "passive"))
      (node (ref "C3") (pin "1") (pinfunction "1_1") (pintype "passive"))
      (node (ref "C30") (pin "1") (pinfunction "1_1") (pintype "passive"))
      (node (ref "C31") (pin "1") (pinfunction "1_1") (pintype "passive"))
      (node (ref "C32") (pin "1") (pinfunction "1_1") (pintype "passive"))
      (node (ref "C33") (pin "1") (pinfunction "1_1") (pintype "passive"))
      (node (ref "C34") (pin "2") (pinfunction "2_2") (pintype "passive"))
      (node (ref "C35") (pin "2") (pinfunction "2_2") (pintype "passive"))
      (node (ref "C36") (pin "2") (pinfunction "2_2") (pintype "passive"))
      (node (ref "C37") (pin "2") (pinfunction "2_2") (pintype "passive"))
      (node (ref "C38") (pin "1") (pinfunction "1_1") (pintype "passive"))
      (node (ref "C39") (pin "1") (pinfunction "1_1") (pintype "passive"))
      (node (ref "C4") (pin "1") (pinfunction "1_1") (pintype "passive"))
      (node (ref "C40") (pin "1") (pinfunction "1_1") (pintype "passive"))
      (node (ref "C41") (pin "1") (pinfunction "1_1") (pintype "passive"))
      (node (ref "C42") (pin "1") (pinfunction "1_1") (pintype "passive"))
      (node (ref "C43") (pin "1") (pinfunction "1_1") (pintype "passive"))
      (node (ref "C44") (pin "1") (pinfunction "1_1") (pintype "passive"))
      (node (ref "C45") (pin "1") (pinfunction "1_1") (pintype "passive"))
      (node (ref "C46") (pin "1") (pinfunction "1_1") (pintype "passive"))
      (node (ref "C47") (pin "1") (pinfunction "1_1") (pintype "passive"))
      (node (ref "C5") (pin "1") (pinfunction "1_1") (pintype "passive"))
      (node (ref "C52") (pin "1") (pinfunction "1_1") (pintype "passive"))
      (node (ref "C53") (pin "1") (pinfunction "1_1") (pintype "passive"))
      (node (ref "C54") (pin "1") (pinfunction "1_1") (pintype "passive"))
      (node (ref "C55") (pin "1") (pinfunction "1_1") (pintype "passive"))
      (node (ref "C56") (pin "1") (pinfunction "1_1") (pintype "passive"))
      (node (ref "C57") (pin "1") (pinfunction "1_1") (pintype "passive"))
      (node (ref "C58") (pin "1") (pinfunction "1_1") (pintype "passive"))
      (node (ref "C59") (pin "1") (pinfunction "1_1") (pintype "passive"))
      (node (ref "C6") (pin "1") (pinfunction "1_1") (pintype "passive"))
      (node (ref "C60") (pin "1") (pinfunction "1_1") (pintype "passive"))
      (node (ref "C61") (pin "1") (pinfunction "1_1") (pintype "passive"))
      (node (ref "C62") (pin "1") (pinfunction "1_1") (pintype "passive"))
      (node (ref "C63") (pin "1") (pinfunction "1_1") (pintype "passive"))
      (node (ref "C64") (pin "1") (pinfunction "1_1") (pintype "passive"))
      (node (ref "C65") (pin "1") (pinfunction "1_1") (pintype "passive"))
      (node (ref "C7") (pin "2") (pinfunction "2_2") (pintype "passive"))
      (node (ref "C8") (pin "2") (pinfunction "2_2") (pintype "passive"))
      (node (ref "C9") (pin "2") (pinfunction "2_2") (pintype "passive"))
      (node (ref "R1") (pin "2") (pinfunction "2_2") (pintype "passive"))
      (node (ref "R10") (pin "1") (pinfunction "1_1") (pintype "passive"))
      (node (ref "R12") (pin "1") (pinfunction "1_1") (pintype "passive"))
      (node (ref "R14") (pin "1") (pinfunction "1_1") (pintype "passive"))
      (node (ref "R16") (pin "2") (pinfunction "2_2") (pintype "passive"))
      (node (ref "R17") (pin "2") (pinfunction "2_2") (pintype "passive"))
      (node (ref "R18") (pin "2") (pinfunction "2_2") (pintype "passive"))
      (node (ref "R19") (pin "2") (pinfunction "2_2") (pintype "passive"))
      (node (ref "R2") (pin "2") (pinfunction "2_2") (pintype "passive"))
      (node (ref "R22") (pin "3") (pinfunction "3_3") (pintype "passive"))
      (node (ref "R23") (pin "3") (pinfunction "3_3") (pintype "passive"))
      (node (ref "R24") (pin "1") (pinfunction "1_1") (pintype "passive"))
      (node (ref "R26") (pin "1") (pinfunction "1_1") (pintype "passive"))
      (node (ref "R3") (pin "2") (pinfunction "2_2") (pintype "passive"))
      (node (ref "R33") (pin "3") (pinfunction "3_3") (pintype "passive"))
      (node (ref "R34") (pin "3") (pinfunction "3_3") (pintype "passive"))
      (node (ref "R36") (pin "3") (pinfunction "3_3") (pintype "passive"))
      (node (ref "R4") (pin "2") (pinfunction "2_2") (pintype "passive"))
      (node (ref "R5") (pin "2") (pinfunction "2_2") (pintype "passive"))
      (node (ref "R6") (pin "2") (pinfunction "2_2") (pintype "passive"))
      (node (ref "U1") (pin "18") (pinfunction "GND_2_18") (pintype "passive"))
      (node (ref "U1") (pin "29") (pinfunction "EP_29") (pintype "passive"))
      (node (ref "U1") (pin "3") (pinfunction "GND_1_3") (pintype "passive"))
      (node (ref "U2") (pin "18") (pinfunction "GND_2_18") (pintype "passive"))
      (node (ref "U2") (pin "29") (pinfunction "EP_29") (pintype "passive"))
      (node (ref "U2") (pin "3") (pinfunction "GND_1_3") (pintype "passive"))
      (node (ref "U3") (pin "18") (pinfunction "GND_2_18") (pintype "passive"))
      (node (ref "U3") (pin "29") (pinfunction "EP_29") (pintype "passive"))
      (node (ref "U3") (pin "3") (pinfunction "GND_1_3") (pintype "passive"))
      (node (ref "U4") (pin "18") (pinfunction "GND_2_18") (pintype "passive"))
      (node (ref "U4") (pin "29") (pinfunction "EP_29") (pintype "passive"))
      (node (ref "U4") (pin "3") (pinfunction "GND_1_3") (pintype "passive"))
      (node (ref "U5") (pin "18") (pinfunction "GND_2_18") (pintype "passive"))
      (node (ref "U5") (pin "29") (pinfunction "EP_29") (pintype "passive"))
      (node (ref "U5") (pin "3") (pinfunction "GND_1_3") (pintype "passive"))
    )
    (net (code "44") (name "Net-(R20-Pad2)") (class "Default")
      (node (ref "R20") (pin "2") (pinfunction "2_2") (pintype "passive"))
      (node (ref "R33") (pin "1") (pinfunction "1_1") (pintype "passive"))
    )
    (net (code "45") (name "Net-(R21-Pad2)") (class "Default")
      (node (ref "R21") (pin "2") (pinfunction "2_2") (pintype "passive"))
      (node (ref "R34") (pin "1") (pinfunction "1_1") (pintype "passive"))
    )
    (net (code "46") (name "Net-(R22-Pad1)") (class "Default")
      (node (ref "R22") (pin "1") (pinfunction "1_1") (pintype "passive"))
      (node (ref "R8") (pin "2") (pinfunction "2_2") (pintype "passive"))
    )
    (net (code "47") (name "Net-(R23-Pad1)") (class "Default")
      (node (ref "R23") (pin "1") (pinfunction "1_1") (pintype "passive"))
      (node (ref "R9") (pin "2") (pinfunction "2_2") (pintype "passive"))
    )
    (net (code "48") (name "Net-(R35-Pad2)") (class "Default")
      (node (ref "R35") (pin "2") (pinfunction "2_2") (pintype "passive"))
      (node (ref "R36") (pin "1") (pinfunction "1_1") (pintype "passive"))
    )
    (net (code "49") (name "Net-(U1-5VOUT)") (class "Default")
      (node (ref "C26") (pin "2") (pinfunction "2_2") (pintype "passive"))
      (node (ref "U1") (pin "10") (pinfunction "MS2_10") (pintype "passive"))
      (node (ref "U1") (pin "8") (pinfunction "5VOUT_8") (pintype "passive"))
      (node (ref "U1") (pin "9") (pinfunction "MS1_9") (pintype "passive"))
    )
    (net (code "50") (name "Net-(U1-BRA)") (class "Default")
      (node (ref "C8") (pin "1") (pinfunction "1_1") (pintype "passive"))
      (node (ref "R2") (pin "1") (pinfunction "1_1") (pintype "passive"))
      (node (ref "U1") (pin "23") (pinfunction "BRA_23") (pintype "passive"))
    )
    (net (code "51") (name "Net-(U1-BRB)") (class "Default")
      (node (ref "C7") (pin "1") (pinfunction "1_1") (pintype "passive"))
      (node (ref "R1") (pin "1") (pinfunction "1_1") (pintype "passive"))
      (node (ref "U1") (pin "27") (pinfunction "BRB_27") (pintype "passive"))
    )
    (net (code "52") (name "Net-(U1-CLK)") (class "Default")
      (node (ref "R10") (pin "2") (pinfunction "2_2") (pintype "passive"))
      (node (ref "U1") (pin "13") (pinfunction "CLK_13") (pintype "passive"))
    )
    (net (code "53") (name "Net-(U1-CPI)") (class "Default")
      (node (ref "C16") (pin "2") (pinfunction "2_2") (pintype "passive"))
      (node (ref "U1") (pin "5") (pinfunction "CPI_5") (pintype "passive"))
    )
    (net (code "54") (name "Net-(U1-CPO)") (class "Default")
      (node (ref "C16") (pin "1") (pinfunction "1_1") (pintype "passive"))
      (node (ref "U1") (pin "4") (pinfunction "CPO_4") (pintype "passive"))
    )
    (net (code "55") (name "Net-(U1-DIAG)") (class "Default")
      (node (ref "D2") (pin "1") (pinfunction "1_1") (pintype "passive"))
      (node (ref "U1") (pin "11") (pinfunction "DIAG_11") (pintype "passive"))
    )
    (net (code "56") (name "Net-(U1-VCP)") (class "Default")
      (node (ref "C19") (pin "2") (pinfunction "2_2") (pintype "passive"))
      (node (ref "U1") (pin "6") (pinfunction "VCP_6") (pintype "passive"))
    )
    (net (code "57") (name "Net-(U1-VREF)") (class "Default")
      (node (ref "R23") (pin "2") (pinfunction "2_2") (pintype "passive"))
      (node (ref "U1") (pin "17") (pinfunction "VREF_17") (pintype "passive"))
    )
    (net (code "58") (name "Net-(U2-5VOUT)") (class "Default")
      (node (ref "C25") (pin "2") (pinfunction "2_2") (pintype "passive"))
      (node (ref "U2") (pin "10") (pinfunction "MS2_10") (pintype "passive"))
      (node (ref "U2") (pin "8") (pinfunction "5VOUT_8") (pintype "passive"))
      (node (ref "U2") (pin "9") (pinfunction "MS1_9") (pintype "passive"))
    )
    (net (code "59") (name "Net-(U2-BRA)") (class "Default")
      (node (ref "C10") (pin "1") (pinfunction "1_1") (pintype "passive"))
      (node (ref "R4") (pin "1") (pinfunction "1_1") (pintype "passive"))
      (node (ref "U2") (pin "23") (pinfunction "BRA_23") (pintype "passive"))
    )
    (net (code "60") (name "Net-(U2-BRB)") (class "Default")
      (node (ref "C9") (pin "1") (pinfunction "1_1") (pintype "passive"))
      (node (ref "R3") (pin "1") (pinfunction "1_1") (pintype "passive"))
      (node (ref "U2") (pin "27") (pinfunction "BRB_27") (pintype "passive"))
    )
    (net (code "61") (name "Net-(U2-CLK)") (class "Default")
      (node (ref "R12") (pin "2") (pinfunction "2_2") (pintype "passive"))
      (node (ref "U2") (pin "13") (pinfunction "CLK_13") (pintype "passive"))
    )
    (net (code "62") (name "Net-(U2-CPI)") (class "Default")
      (node (ref "C17") (pin "2") (pinfunction "2_2") (pintype "passive"))
      (node (ref "U2") (pin "5") (pinfunction "CPI_5") (pintype "passive"))
    )
    (net (code "63") (name "Net-(U2-CPO)") (class "Default")
      (node (ref "C17") (pin "1") (pinfunction "1_1") (pintype "passive"))
      (node (ref "U2") (pin "4") (pinfunction "CPO_4") (pintype "passive"))
    )
    (net (code "64") (name "Net-(U2-DIAG)") (class "Default")
      (node (ref "D4") (pin "1") (pinfunction "1_1") (pintype "passive"))
      (node (ref "U2") (pin "11") (pinfunction "DIAG_11") (pintype "passive"))
    )
    (net (code "65") (name "Net-(U2-VCP)") (class "Default")
      (node (ref "C20") (pin "2") (pinfunction "2_2") (pintype "passive"))
      (node (ref "U2") (pin "6") (pinfunction "VCP_6") (pintype "passive"))
    )
    (net (code "66") (name "Net-(U2-VREF)") (class "Default")
      (node (ref "R34") (pin "2") (pinfunction "2_2") (pintype "passive"))
      (node (ref "U2") (pin "17") (pinfunction "VREF_17") (pintype "passive"))
    )
    (net (code "67") (name "Net-(U3-5VOUT)") (class "Default")
      (node (ref "C27") (pin "2") (pinfunction "2_2") (pintype "passive"))
      (node (ref "U3") (pin "10") (pinfunction "MS2_10") (pintype "passive"))
      (node (ref "U3") (pin "8") (pinfunction "5VOUT_8") (pintype "passive"))
      (node (ref "U3") (pin "9") (pinfunction "MS1_9") (pintype "passive"))
    )
    (net (code "68") (name "Net-(U3-BRA)") (class "Default")
      (node (ref "C15") (pin "1") (pinfunction "1_1") (pintype "passive"))
      (node (ref "R6") (pin "1") (pinfunction "1_1") (pintype "passive"))
      (node (ref "U3") (pin "23") (pinfunction "BRA_23") (pintype "passive"))
    )
    (net (code "69") (name "Net-(U3-BRB)") (class "Default")
      (node (ref "C14") (pin "1") (pinfunction "1_1") (pintype "passive"))
      (node (ref "R5") (pin "1") (pinfunction "1_1") (pintype "passive"))
      (node (ref "U3") (pin "27") (pinfunction "BRB_27") (pintype "passive"))
    )
    (net (code "70") (name "Net-(U3-CLK)") (class "Default")
      (node (ref "R14") (pin "2") (pinfunction "2_2") (pintype "passive"))
      (node (ref "U3") (pin "13") (pinfunction "CLK_13") (pintype "passive"))
    )
    (net (code "71") (name "Net-(U3-CPI)") (class "Default")
      (node (ref "C18") (pin "2") (pinfunction "2_2") (pintype "passive"))
      (node (ref "U3") (pin "5") (pinfunction "CPI_5") (pintype "passive"))
    )
    (net (code "72") (name "Net-(U3-CPO)") (class "Default")
      (node (ref "C18") (pin "1") (pinfunction "1_1") (pintype "passive"))
      (node (ref "U3") (pin "4") (pinfunction "CPO_4") (pintype "passive"))
    )
    (net (code "73") (name "Net-(U3-DIAG)") (class "Default")
      (node (ref "D5") (pin "1") (pinfunction "1_1") (pintype "passive"))
      (node (ref "U3") (pin "11") (pinfunction "DIAG_11") (pintype "passive"))
    )
    (net (code "74") (name "Net-(U3-VCP)") (class "Default")
      (node (ref "C23") (pin "2") (pinfunction "2_2") (pintype "passive"))
      (node (ref "U3") (pin "6") (pinfunction "VCP_6") (pintype "passive"))
    )
    (net (code "75") (name "Net-(U3-VREF)") (class "Default")
      (node (ref "R36") (pin "2") (pinfunction "2_2") (pintype "passive"))
      (node (ref "U3") (pin "17") (pinfunction "VREF_17") (pintype "passive"))
    )
    (net (code "76") (name "Net-(U4-5VOUT)") (class "Default")
      (node (ref "C64") (pin "2") (pinfunction "2_2") (pintype "passive"))
      (node (ref "U4") (pin "10") (pinfunction "MS2_10") (pintype "passive"))
      (node (ref "U4") (pin "8") (pinfunction "5VOUT_8") (pintype "passive"))
      (node (ref "U4") (pin "9") (pinfunction "MS1_9") (pintype "passive"))
    )
    (net (code "77") (name "Net-(U4-BRA)") (class "Default")
      (node (ref "C35") (pin "1") (pinfunction "1_1") (pintype "passive"))
      (node (ref "R17") (pin "1") (pinfunction "1_1") (pintype "passive"))
      (node (ref "U4") (pin "23") (pinfunction "BRA_23") (pintype "passive"))
    )
    (net (code "78") (name "Net-(U4-BRB)") (class "Default")
      (node (ref "C34") (pin "1") (pinfunction "1_1") (pintype "passive"))
      (node (ref "R16") (pin "1") (pinfunction "1_1") (pintype "passive"))
      (node (ref "U4") (pin "27") (pinfunction "BRB_27") (pintype "passive"))
    )
    (net (code "79") (name "Net-(U4-CLK)") (class "Default")
      (node (ref "R24") (pin "2") (pinfunction "2_2") (pintype "passive"))
      (node (ref "U4") (pin "13") (pinfunction "CLK_13") (pintype "passive"))
    )
    (net (code "80") (name "Net-(U4-CPI)") (class "Default")
      (node (ref "C48") (pin "2") (pinfunction "2_2") (pintype "passive"))
      (node (ref "U4") (pin "5") (pinfunction "CPI_5") (pintype "passive"))
    )
    (net (code "81") (name "Net-(U4-CPO)") (class "Default")
      (node (ref "C48") (pin "1") (pinfunction "1_1") (pintype "passive"))
      (node (ref "U4") (pin "4") (pinfunction "CPO_4") (pintype "passive"))
    )
    (net (code "82") (name "Net-(U4-DIAG)") (class "Default")
      (node (ref "D3") (pin "1") (pinfunction "1_1") (pintype "passive"))
      (node (ref "U4") (pin "11") (pinfunction "DIAG_11") (pintype "passive"))
    )
    (net (code "83") (name "Net-(U4-VCP)") (class "Default")
      (node (ref "C50") (pin "2") (pinfunction "2_2") (pintype "passive"))
      (node (ref "U4") (pin "6") (pinfunction "VCP_6") (pintype "passive"))
    )
    (net (code "84") (name "Net-(U4-VREF)") (class "Default")
      (node (ref "R33") (pin "2") (pinfunction "2_2") (pintype "passive"))
      (node (ref "U4") (pin "17") (pinfunction "VREF_17") (pintype "passive"))
    )
    (net (code "85") (name "Net-(U5-5VOUT)") (class "Default")
      (node (ref "C65") (pin "2") (pinfunction "2_2") (pintype "passive"))
      (node (ref "U5") (pin "10") (pinfunction "MS2_10") (pintype "passive"))
      (node (ref "U5") (pin "8") (pinfunction "5VOUT_8") (pintype "passive"))
      (node (ref "U5") (pin "9") (pinfunction "MS1_9") (pintype "passive"))
    )
    (net (code "86") (name "Net-(U5-BRA)") (class "Default")
      (node (ref "C37") (pin "1") (pinfunction "1_1") (pintype "passive"))
      (node (ref "R19") (pin "1") (pinfunction "1_1") (pintype "passive"))
      (node (ref "U5") (pin "23") (pinfunction "BRA_23") (pintype "passive"))
    )
    (net (code "87") (name "Net-(U5-BRB)") (class "Default")
      (node (ref "C36") (pin "1") (pinfunction "1_1") (pintype "passive"))
      (node (ref "R18") (pin "1") (pinfunction "1_1") (pintype "passive"))
      (node (ref "U5") (pin "27") (pinfunction "BRB_27") (pintype "passive"))
    )
    (net (code "88") (name "Net-(U5-CLK)") (class "Default")
      (node (ref "R26") (pin "2") (pinfunction "2_2") (pintype "passive"))
      (node (ref "U5") (pin "13") (pinfunction "CLK_13") (pintype "passive"))
    )
    (net (code "89") (name "Net-(U5-CPI)") (class "Default")
      (node (ref "C49") (pin "2") (pinfunction "2_2") (pintype "passive"))
      (node (ref "U5") (pin "5") (pinfunction "CPI_5") (pintype "passive"))
    )
    (net (code "90") (name "Net-(U5-CPO)") (class "Default")
      (node (ref "C49") (pin "1") (pinfunction "1_1") (pintype "passive"))
      (node (ref "U5") (pin "4") (pinfunction "CPO_4") (pintype "passive"))
    )
    (net (code "91") (name "Net-(U5-DIAG)") (class "Default")
      (node (ref "D1") (pin "1") (pinfunction "1_1") (pintype "passive"))
      (node (ref "U5") (pin "11") (pinfunction "DIAG_11") (pintype "passive"))
    )
    (net (code "92") (name "Net-(U5-VCP)") (class "Default")
      (node (ref "C51") (pin "2") (pinfunction "2_2") (pintype "passive"))
      (node (ref "U5") (pin "6") (pinfunction "VCP_6") (pintype "passive"))
    )
    (net (code "93") (name "Net-(U5-VREF)") (class "Default")
      (node (ref "R22") (pin "2") (pinfunction "2_2") (pintype "passive"))
      (node (ref "U5") (pin "17") (pinfunction "VREF_17") (pintype "passive"))
    )
    (net (code "94") (name "unconnected-(U1-INDEX-Pad12)") (class "Default")
      (node (ref "U1") (pin "12") (pinfunction "INDEX_12") (pintype "passive+no_connect"))
    )
    (net (code "95") (name "unconnected-(U1-NC_1-Pad7)") (class "Default")
      (node (ref "U1") (pin "7") (pinfunction "NC_1_7") (pintype "passive+no_connect"))
    )
    (net (code "96") (name "unconnected-(U1-NC_2-Pad20)") (class "Default")
      (node (ref "U1") (pin "20") (pinfunction "NC_2_20") (pintype "passive+no_connect"))
    )
    (net (code "97") (name "unconnected-(U1-NC_3-Pad25)") (class "Default")
      (node (ref "U1") (pin "25") (pinfunction "NC_3_25") (pintype "passive+no_connect"))
    )
    (net (code "98") (name "unconnected-(U2-INDEX-Pad12)") (class "Default")
      (node (ref "U2") (pin "12") (pinfunction "INDEX_12") (pintype "passive+no_connect"))
    )
    (net (code "99") (name "unconnected-(U2-NC_1-Pad7)") (class "Default")
      (node (ref "U2") (pin "7") (pinfunction "NC_1_7") (pintype "passive+no_connect"))
    )
    (net (code "100") (name "unconnected-(U2-NC_2-Pad20)") (class "Default")
      (node (ref "U2") (pin "20") (pinfunction "NC_2_20") (pintype "passive+no_connect"))
    )
    (net (code "101") (name "unconnected-(U2-NC_3-Pad25)") (class "Default")
      (node (ref "U2") (pin "25") (pinfunction "NC_3_25") (pintype "passive+no_connect"))
    )
    (net (code "102") (name "unconnected-(U3-INDEX-Pad12)") (class "Default")
      (node (ref "U3") (pin "12") (pinfunction "INDEX_12") (pintype "passive+no_connect"))
    )
    (net (code "103") (name "unconnected-(U3-NC_1-Pad7)") (class "Default")
      (node (ref "U3") (pin "7") (pinfunction "NC_1_7") (pintype "passive+no_connect"))
    )
    (net (code "104") (name "unconnected-(U3-NC_2-Pad20)") (class "Default")
      (node (ref "U3") (pin "20") (pinfunction "NC_2_20") (pintype "passive+no_connect"))
    )
    (net (code "105") (name "unconnected-(U3-NC_3-Pad25)") (class "Default")
      (node (ref "U3") (pin "25") (pinfunction "NC_3_25") (pintype "passive+no_connect"))
    )
    (net (code "106") (name "unconnected-(U4-INDEX-Pad12)") (class "Default")
      (node (ref "U4") (pin "12") (pinfunction "INDEX_12") (pintype "passive+no_connect"))
    )
    (net (code "107") (name "unconnected-(U4-NC_1-Pad7)") (class "Default")
      (node (ref "U4") (pin "7") (pinfunction "NC_1_7") (pintype "passive+no_connect"))
    )
    (net (code "108") (name "unconnected-(U4-NC_2-Pad20)") (class "Default")
      (node (ref "U4") (pin "20") (pinfunction "NC_2_20") (pintype "passive+no_connect"))
    )
    (net (code "109") (name "unconnected-(U4-NC_3-Pad25)") (class "Default")
      (node (ref "U4") (pin "25") (pinfunction "NC_3_25") (pintype "passive+no_connect"))
    )
    (net (code "110") (name "unconnected-(U5-INDEX-Pad12)") (class "Default")
      (node (ref "U5") (pin "12") (pinfunction "INDEX_12") (pintype "passive+no_connect"))
    )
    (net (code "111") (name "unconnected-(U5-NC_1-Pad7)") (class "Default")
      (node (ref "U5") (pin "7") (pinfunction "NC_1_7") (pintype "passive+no_connect"))
    )
    (net (code "112") (name "unconnected-(U5-NC_2-Pad20)") (class "Default")
      (node (ref "U5") (pin "20") (pinfunction "NC_2_20") (pintype "passive+no_connect"))
    )
    (net (code "113") (name "unconnected-(U5-NC_3-Pad25)") (class "Default")
      (node (ref "U5") (pin "25") (pinfunction "NC_3_25") (pintype "passive+no_connect"))
    )
  )
)
